# Safety_Loop.net
KiCad netlist of a schematic drawn in Altium Designer
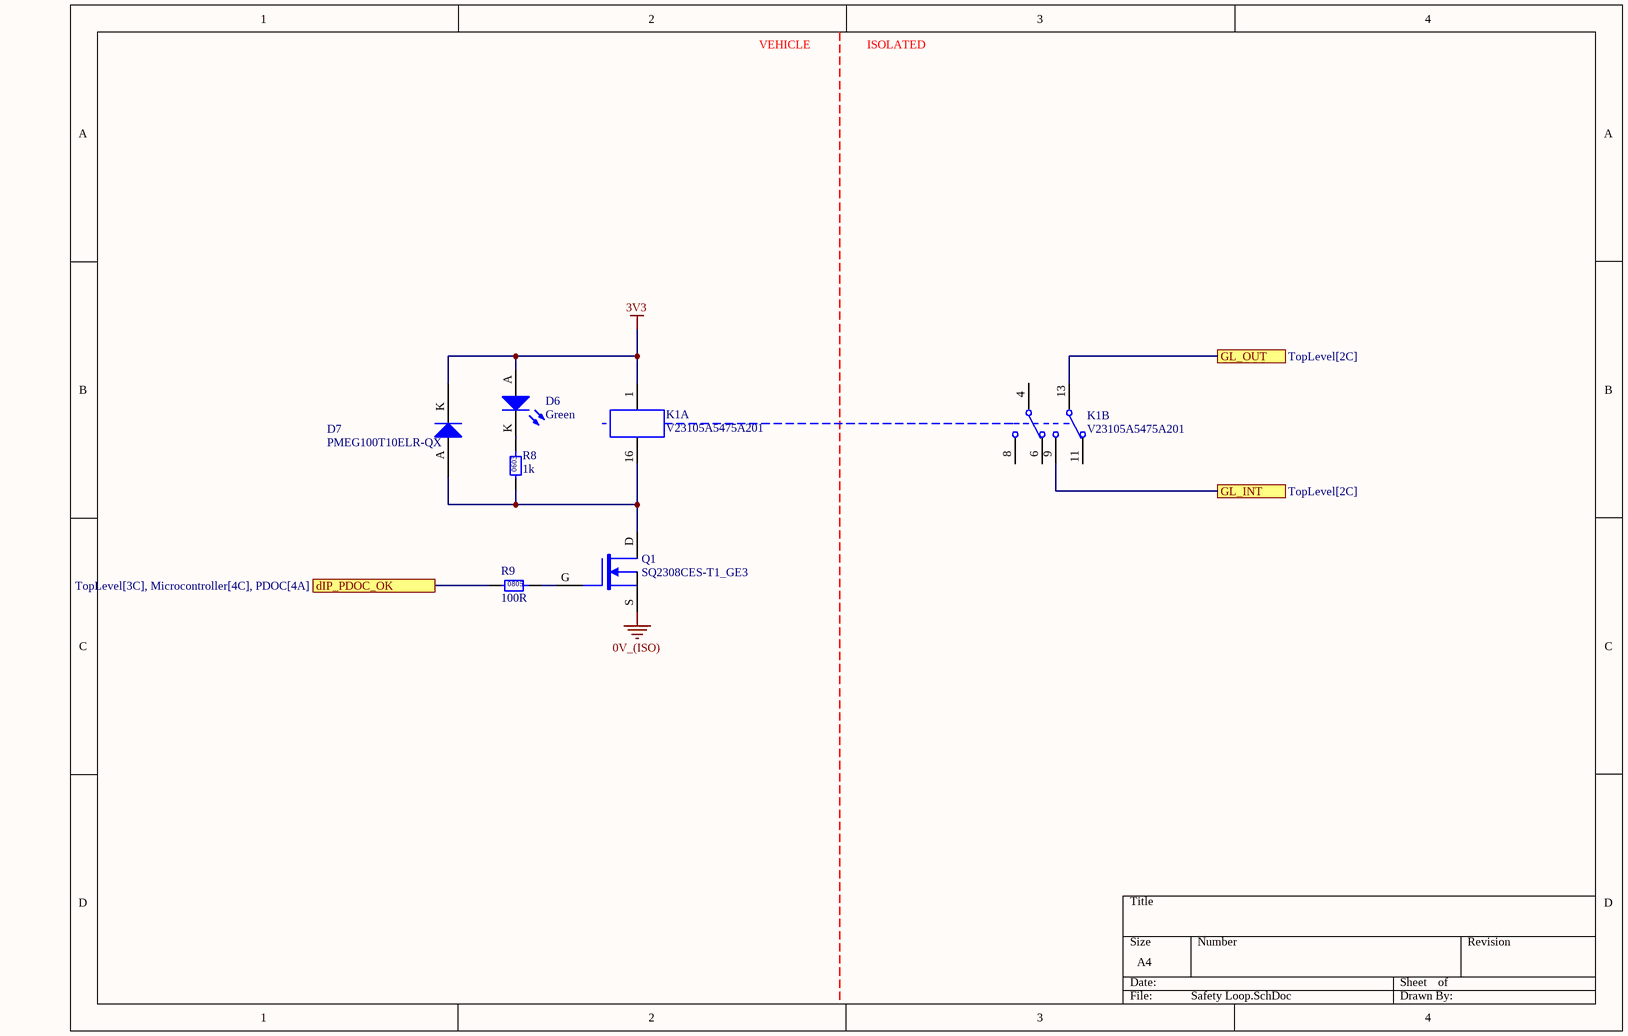
[diagram p0: Safety Loop.SchDoc]

(export (version "E")
  (design (tool "Eeschema 10.0.6"))
  (components
    (comp (ref "D6")
      (value "Green")
      (footprint "0805 LED")
      (description "Green LED Indication - Discrete 1.75V 0805 (2012 Metric)")
      (fields (field (name "PART NUMBER") "SML-210FTT86") (field (name "MANUFACTURER") "ROHM Semiconductor"))
      (libsource (lib "ts_standard_library") (part "LED"))
    )
    (comp (ref "D7")
      (value "PMEG100T10ELR-QX")
      (footprint "SODFL350X110-2N")
      (description "Diode 100 V 1A Surface Mount SOD-123W")
      (libsource (lib "Team Swinburne") (part "PMEG100T10ELR-QX"))
    )
    (comp (ref "K1")
      (value "V23105A5475A201")
      (footprint "TI 2-DIL")
      (description "5V DPDT Relay 3A 220VDC")
      (libsource (lib "") (part "Symbol_1"))
    )
    (comp (ref "Q1")
      (value "SQ2308CES-T1_GE3")
      (footprint "VSHY SOT-23-3")
      (description "MOSFET N-CH 60V 2.3A SOT23")
      (fields
        (field (name "MANUFACTURER") "Vishay Siliconix")
        (field (name "DIGIKEY PART NUMBER") "SQ2308CES-T1_GE3CT-ND")
        (field (name "PUBLISHER") "Altium Limited")
      )
      (libsource (lib "ts_standard_library") (part "MOSFET-N"))
    )
    (comp (ref "R8")
      (value "1k")
      (footprint "0603")
      (fields
        (field (name "PART NUMBER") "RC0603FR-071KL")
        (field (name "MANUFACTURER") "YAGEO")
        (field (name "TOLERANCE") "0.01")
      )
      (libsource (lib "ts_standard_library") (part "Resistor 0603"))
    )
    (comp (ref "R9")
      (value "100R")
      (footprint "0805")
      (fields
        (field (name "PART NUMBER") "RC0805FR07100RL")
        (field (name "MANUFACTURER") "YAGEO")
        (field (name "TOLERANCE") "0.01")
      )
      (libsource (lib "ts_standard_library") (part "Resistor 0805"))
    )
  )
  (nets
    (net (code "1") (name "/GL_INT") (class "Default")
      (node (ref "K1") (pin "9") (pinfunction "9_9") (pintype "passive"))
    )
    (net (code "2") (name "/GL_OUT") (class "Default")
      (node (ref "K1") (pin "13") (pinfunction "13_13") (pintype "passive"))
    )
    (net (code "3") (name "/dIP_PDOC_OK") (class "Default")
      (node (ref "R9") (pin "1") (pinfunction "1_1") (pintype "passive"))
    )
    (net (code "4") (name "0V_(ISO)") (class "Default")
      (node (ref "Q1") (pin "S") (pinfunction "S_S") (pintype "passive"))
    )
    (net (code "5") (name "3V3") (class "Default")
      (node (ref "D6") (pin "A") (pinfunction "A_A") (pintype "passive"))
      (node (ref "D7") (pin "K") (pintype "passive"))
      (node (ref "K1") (pin "1") (pinfunction "1_1") (pintype "passive"))
    )
    (net (code "6") (name "Net-(D6-PadK)") (class "Default")
      (node (ref "D6") (pin "K") (pinfunction "K_K") (pintype "passive"))
      (node (ref "R8") (pin "2") (pinfunction "2_2") (pintype "passive"))
    )
    (net (code "7") (name "Net-(D7-PadA)") (class "Default")
      (node (ref "D7") (pin "A") (pintype "passive"))
      (node (ref "K1") (pin "16") (pinfunction "16_16") (pintype "passive"))
      (node (ref "Q1") (pin "D") (pinfunction "D_D") (pintype "passive"))
      (node (ref "R8") (pin "1") (pinfunction "1_1") (pintype "passive"))
    )
    (net (code "8") (name "Net-(Q1-PadG)") (class "Default")
      (node (ref "Q1") (pin "G") (pinfunction "G_G") (pintype "passive"))
      (node (ref "R9") (pin "2") (pinfunction "2_2") (pintype "passive"))
    )
    (net (code "9") (name "unconnected-(K1-Pad4)") (class "Default")
      (node (ref "K1") (pin "4") (pinfunction "4_4") (pintype "passive"))
    )
    (net (code "10") (name "unconnected-(K1-Pad6)") (class "Default")
      (node (ref "K1") (pin "6") (pinfunction "6_6") (pintype "passive"))
    )
    (net (code "11") (name "unconnected-(K1-Pad8)") (class "Default")
      (node (ref "K1") (pin "8") (pinfunction "8_8") (pintype "passive"))
    )
    (net (code "12") (name "unconnected-(K1-Pad11)") (class "Default")
      (node (ref "K1") (pin "11") (pinfunction "11_11") (pintype "passive"))
    )
  )
)
